# Dual_Motor_Driver.net
KiCad netlist of a schematic drawn in EAGLE
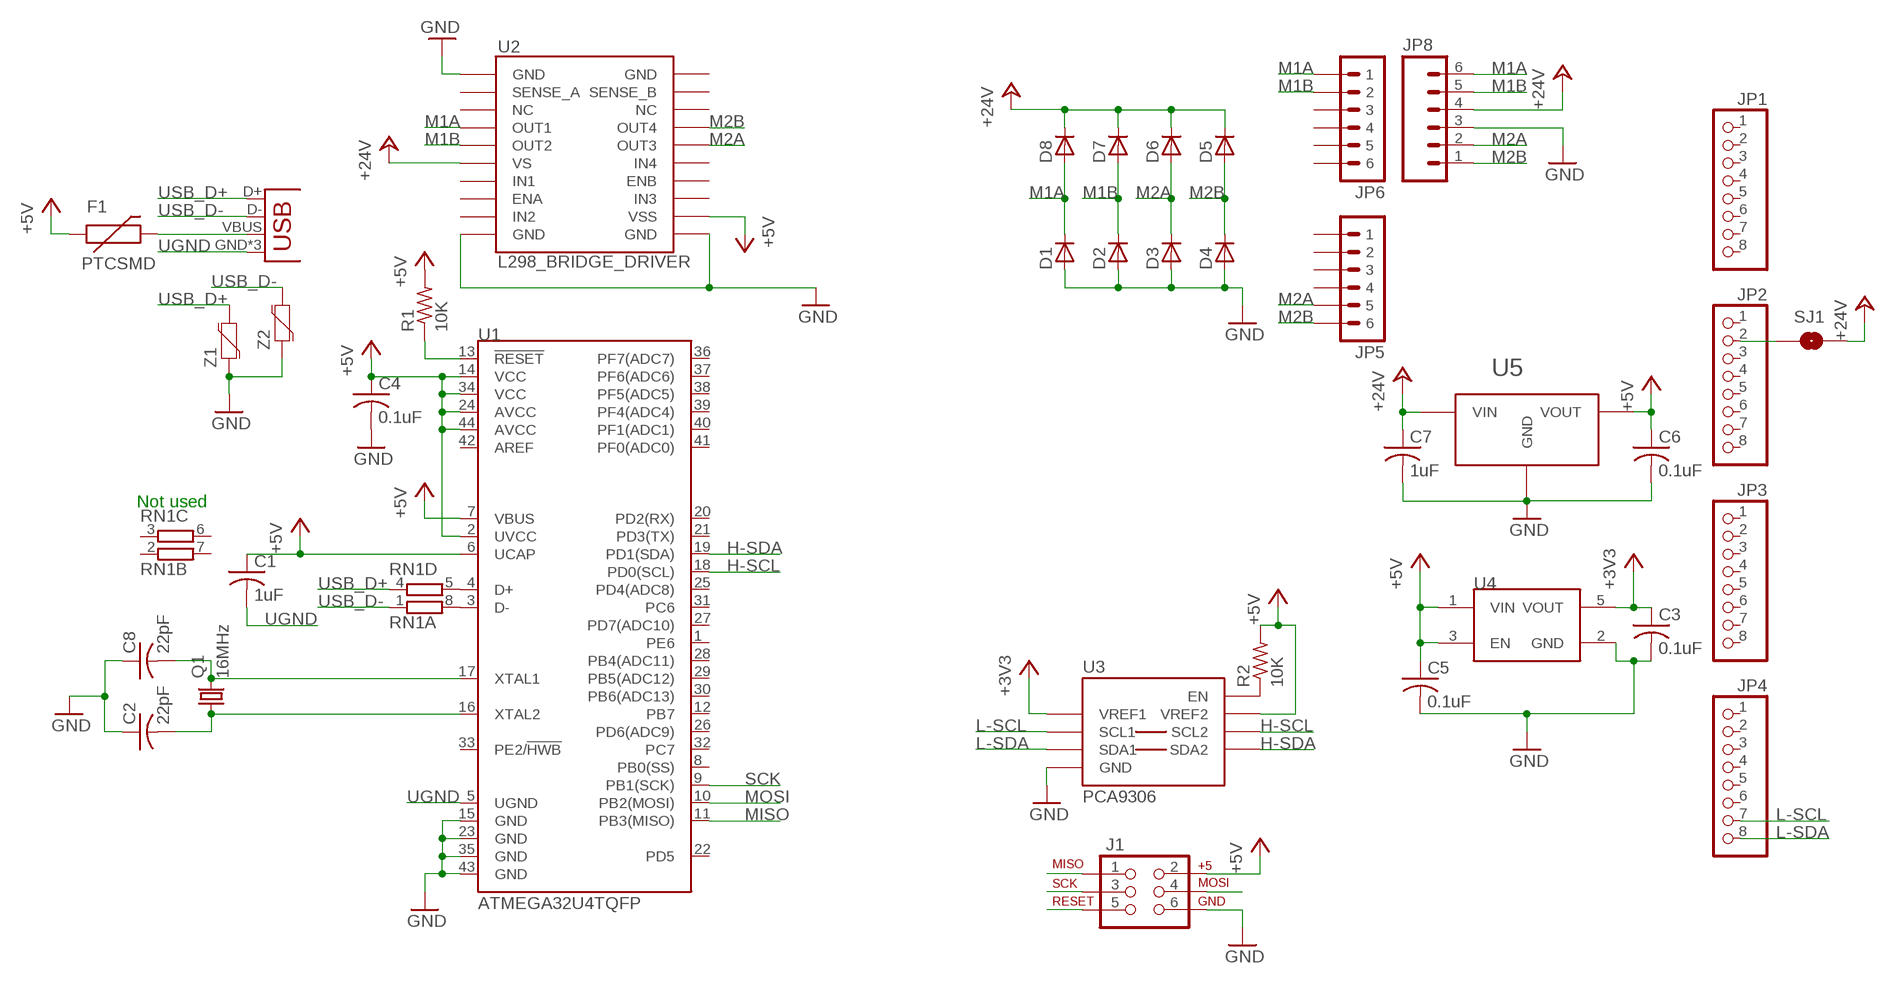
[diagram p0: schematic, sheet 1]

(export (version "E")
  (design (tool "Eeschema 10.0.6"))
  (components
    (comp (ref "C1")
      (value "1uF")
      (footprint "eagle-import:C0603")
      (libsource (lib "eagle-import") (part "C-USC0603"))
    )
    (comp (ref "C2")
      (value "22pF")
      (footprint "eagle-import:C0603")
      (libsource (lib "eagle-import") (part "C-USC0603"))
    )
    (comp (ref "C3")
      (value "0.1uF")
      (footprint "eagle-import:C0603")
      (libsource (lib "eagle-import") (part "C-USC0603"))
    )
    (comp (ref "C4")
      (value "0.1uF")
      (footprint "eagle-import:C0603")
      (libsource (lib "eagle-import") (part "C-USC0603"))
    )
    (comp (ref "C5")
      (value "0.1uF")
      (footprint "eagle-import:C0603")
      (libsource (lib "eagle-import") (part "C-USC0603"))
    )
    (comp (ref "C6")
      (value "0.1uF")
      (footprint "eagle-import:C0603")
      (libsource (lib "eagle-import") (part "C-USC0603"))
    )
    (comp (ref "C7")
      (value "1uF")
      (footprint "eagle-import:C0603")
      (libsource (lib "eagle-import") (part "C-USC0603"))
    )
    (comp (ref "C8")
      (value "22pF")
      (footprint "eagle-import:C0603")
      (libsource (lib "eagle-import") (part "C-USC0603"))
    )
    (comp (ref "D1")
      (value "D-SOD123")
      (footprint "eagle-import:SOD123")
      (fields (field (name "PART#") "CDBW140-G"))
      (libsource (lib "eagle-import") (part "D-SOD123"))
    )
    (comp (ref "D2")
      (value "D-SOD123")
      (footprint "eagle-import:SOD123")
      (fields (field (name "PART#") "CDBW140-G"))
      (libsource (lib "eagle-import") (part "D-SOD123"))
    )
    (comp (ref "D3")
      (value "D-SOD123")
      (footprint "eagle-import:SOD123")
      (fields (field (name "PART#") "CDBW140-G"))
      (libsource (lib "eagle-import") (part "D-SOD123"))
    )
    (comp (ref "D4")
      (value "D-SOD123")
      (footprint "eagle-import:SOD123")
      (fields (field (name "PART#") "CDBW140-G"))
      (libsource (lib "eagle-import") (part "D-SOD123"))
    )
    (comp (ref "D5")
      (value "D-SOD123")
      (footprint "eagle-import:SOD123")
      (fields (field (name "PART#") "CDBW140-G"))
      (libsource (lib "eagle-import") (part "D-SOD123"))
    )
    (comp (ref "D6")
      (value "D-SOD123")
      (footprint "eagle-import:SOD123")
      (fields (field (name "PART#") "CDBW140-G"))
      (libsource (lib "eagle-import") (part "D-SOD123"))
    )
    (comp (ref "D7")
      (value "D-SOD123")
      (footprint "eagle-import:SOD123")
      (fields (field (name "PART#") "CDBW140-G"))
      (libsource (lib "eagle-import") (part "D-SOD123"))
    )
    (comp (ref "D8")
      (value "D-SOD123")
      (footprint "eagle-import:SOD123")
      (fields (field (name "PART#") "CDBW140-G"))
      (libsource (lib "eagle-import") (part "D-SOD123"))
    )
    (comp (ref "F1")
      (value "PTCSMD")
      (footprint "eagle-import:PTC-1206")
      (fields (field (name "PART#") "0ZCJ0050FF2G"))
      (libsource (lib "eagle-import") (part "PTCSMD"))
    )
    (comp (ref "J1")
      (value "AVR_SPI_PRG_6PTH")
      (footprint "eagle-import:2X3")
      (libsource (lib "eagle-import") (part "AVR_SPI_PRG_6PTH"))
    )
    (comp (ref "JP1")
      (value "PINHD-1X81X08_NO_SILK")
      (footprint "eagle-import:1X08_NO_SS")
      (libsource (lib "eagle-import") (part "PINHD-1X81X08_NO_SILK"))
    )
    (comp (ref "JP2")
      (value "PINHD-1X81X08_NO_SILK")
      (footprint "eagle-import:1X08_NO_SS")
      (libsource (lib "eagle-import") (part "PINHD-1X81X08_NO_SILK"))
    )
    (comp (ref "JP3")
      (value "PINHD-1X81X08_NO_SILK")
      (footprint "eagle-import:1X08_NO_SS")
      (libsource (lib "eagle-import") (part "PINHD-1X81X08_NO_SILK"))
    )
    (comp (ref "JP4")
      (value "PINHD-1X81X08_NO_SILK")
      (footprint "eagle-import:1X08_NO_SS")
      (libsource (lib "eagle-import") (part "PINHD-1X81X08_NO_SILK"))
    )
    (comp (ref "JP5")
      (value "6PIN-SH_RIGHT_ANGLE")
      (footprint "eagle-import:6PIN-SH_SERIES_RA")
      (fields (field (name "PART#") "SM06B-SRSS-TB(LF)(SN)"))
      (libsource (lib "eagle-import") (part "6PIN-SH_RIGHT_ANGLE"))
    )
    (comp (ref "JP6")
      (value "6PIN-SH_RIGHT_ANGLE")
      (footprint "eagle-import:6PIN-SH_SERIES_RA")
      (fields (field (name "PART#") "SM06B-SRSS-TB(LF)(SN)"))
      (libsource (lib "eagle-import") (part "6PIN-SH_RIGHT_ANGLE"))
    )
    (comp (ref "JP7")
      (value "USB-MICROB")
      (footprint "eagle-import:USB-MICROB")
      (libsource (lib "eagle-import") (part "USB-MICROB"))
    )
    (comp (ref "JP8")
      (value "M063.5MM-6")
      (footprint "eagle-import:SCREWTERMINAL-3.5MM-6")
      (libsource (lib "eagle-import") (part "M063.5MM-6"))
    )
    (comp (ref "Q1")
      (value "16MHz")
      (footprint "eagle-import:CTS406")
      (fields (field (name "PART#") "406C35D16M00000"))
      (libsource (lib "eagle-import") (part "CRYSTALCTS406"))
    )
    (comp (ref "R1")
      (value "10K")
      (footprint "eagle-import:R0603")
      (libsource (lib "eagle-import") (part "R-US_R0603"))
    )
    (comp (ref "R2")
      (value "10K")
      (footprint "eagle-import:R0603")
      (libsource (lib "eagle-import") (part "R-US_R0603"))
    )
    (comp (ref "RN1")
      (value "4R-N0603-ARV")
      (footprint "eagle-import:0603-ARV")
      (libsource (lib "eagle-import") (part "4R-N0603-ARV"))
    )
    (comp (ref "SJ1")
      (value "SOLDERJUMPERNC")
      (footprint "eagle-import:SJ_2S")
      (libsource (lib "eagle-import") (part "SOLDERJUMPERNC"))
    )
    (comp (ref "U1")
      (value "ATMEGA32U4TQFP")
      (footprint "eagle-import:SPARKFUN-DIGITALIC_TQFP44")
      (libsource (lib "eagle-import") (part "ATMEGA32U4TQFP"))
    )
    (comp (ref "U2")
      (value "L298_BRIDGE_DRIVER")
      (footprint "eagle-import:POWERSO20")
      (libsource (lib "eagle-import") (part "L298_BRIDGE_DRIVER"))
    )
    (comp (ref "U3")
      (value "PCA9306")
      (footprint "eagle-import:SOIC-8")
      (fields (field (name "PART#") "PCA9306D,118"))
      (libsource (lib "eagle-import") (part "PCA9306"))
    )
    (comp (ref "U4")
      (value "TLV71333PDBVR")
      (footprint "eagle-import:SOT23-5")
      (libsource (lib "eagle-import") (part "ADP160"))
    )
    (comp (ref "U5")
      (value "VOLTAGE-REGULATOR")
      (footprint "eagle-import:SOT89")
      (fields (field (name "PART#") "L78L05ACUTR"))
      (libsource (lib "eagle-import") (part "VOLTAGE-REGULATOR"))
    )
    (comp (ref "Z1")
      (value "VARISTOR-0603")
      (footprint "eagle-import:0603-RES")
      (fields (field (name "PART#") "CG0603MLC-05E"))
      (libsource (lib "eagle-import") (part "VARISTOR-0603"))
    )
    (comp (ref "Z2")
      (value "VARISTOR-0603")
      (footprint "eagle-import:0603-RES")
      (fields (field (name "PART#") "CG0603MLC-05E"))
      (libsource (lib "eagle-import") (part "VARISTOR-0603"))
    )
  )
  (nets
    (net (code "1") (name "+3V3") (class "Default")
      (node (ref "C3") (pin "1") (pinfunction "1_1") (pintype "passive"))
      (node (ref "U3") (pin "P$2") (pinfunction "VREF1_P$2") (pintype "bidirectional"))
      (node (ref "U4") (pin "5") (pinfunction "VOUT_5") (pintype "bidirectional"))
    )
    (net (code "2") (name "+5V") (class "Default")
      (node (ref "C1") (pin "1") (pinfunction "1_1") (pintype "passive"))
      (node (ref "C4") (pin "1") (pinfunction "1_1") (pintype "passive"))
      (node (ref "C5") (pin "1") (pinfunction "1_1") (pintype "passive"))
      (node (ref "C6") (pin "1") (pinfunction "1_1") (pintype "passive"))
      (node (ref "F1") (pin "1") (pinfunction "1_1") (pintype "bidirectional"))
      (node (ref "J1") (pin "2") (pinfunction "2_2") (pintype "passive"))
      (node (ref "R1") (pin "2") (pinfunction "2_2") (pintype "passive"))
      (node (ref "R2") (pin "2") (pinfunction "2_2") (pintype "passive"))
      (node (ref "U1") (pin "14") (pinfunction "VCC_14") (pintype "bidirectional"))
      (node (ref "U1") (pin "2") (pinfunction "UVCC_2") (pintype "bidirectional"))
      (node (ref "U1") (pin "24") (pinfunction "AVCC_24") (pintype "bidirectional"))
      (node (ref "U1") (pin "34") (pinfunction "VCC_34") (pintype "bidirectional"))
      (node (ref "U1") (pin "44") (pinfunction "AVCC_44") (pintype "bidirectional"))
      (node (ref "U1") (pin "6") (pinfunction "UCAP_6") (pintype "bidirectional"))
      (node (ref "U1") (pin "7") (pinfunction "VBUS_7") (pintype "bidirectional"))
      (node (ref "U2") (pin "12") (pinfunction "VSS_12") (pintype "bidirectional"))
      (node (ref "U3") (pin "P$7") (pinfunction "VREF2_P$7") (pintype "bidirectional"))
      (node (ref "U4") (pin "1") (pinfunction "VIN_1") (pintype "bidirectional"))
      (node (ref "U4") (pin "3") (pinfunction "EN_3") (pintype "bidirectional"))
      (node (ref "U5") (pin "P$1") (pinfunction "VOUT_P$1") (pintype "bidirectional"))
    )
    (net (code "3") (name "+24V") (class "Default")
      (node (ref "C7") (pin "1") (pinfunction "1_1") (pintype "passive"))
      (node (ref "D5") (pin "1") (pinfunction "C_1") (pintype "passive"))
      (node (ref "D6") (pin "1") (pinfunction "C_1") (pintype "passive"))
      (node (ref "D7") (pin "1") (pinfunction "C_1") (pintype "passive"))
      (node (ref "D8") (pin "1") (pinfunction "C_1") (pintype "passive"))
      (node (ref "JP8") (pin "4") (pinfunction "4_4") (pintype "passive"))
      (node (ref "SJ1") (pin "2") (pinfunction "2_2") (pintype "passive"))
      (node (ref "U2") (pin "6") (pinfunction "VS_6") (pintype "bidirectional"))
      (node (ref "U5") (pin "P$3") (pinfunction "VIN_P$3") (pintype "bidirectional"))
    )
    (net (code "4") (name "/H-SCL") (class "Default")
      (node (ref "U1") (pin "18") (pinfunction "PD0(SCL)_18") (pintype "bidirectional"))
      (node (ref "U3") (pin "P$6") (pinfunction "SCL2_P$6") (pintype "bidirectional"))
    )
    (net (code "5") (name "/H-SDA") (class "Default")
      (node (ref "U1") (pin "19") (pinfunction "PD1(SDA)_19") (pintype "bidirectional"))
      (node (ref "U3") (pin "P$5") (pinfunction "SDA2_P$5") (pintype "bidirectional"))
    )
    (net (code "6") (name "/L-SCL") (class "Default")
      (node (ref "JP4") (pin "7") (pinfunction "7_7") (pintype "passive"))
      (node (ref "U3") (pin "P$3") (pinfunction "SCL1_P$3") (pintype "bidirectional"))
    )
    (net (code "7") (name "/L-SDA") (class "Default")
      (node (ref "JP4") (pin "8") (pinfunction "8_8") (pintype "passive"))
      (node (ref "U3") (pin "P$4") (pinfunction "SDA1_P$4") (pintype "bidirectional"))
    )
    (net (code "8") (name "/M1A") (class "Default")
      (node (ref "D1") (pin "1") (pinfunction "C_1") (pintype "passive"))
      (node (ref "D8") (pin "2") (pinfunction "A_2") (pintype "passive"))
      (node (ref "JP6") (pin "P$1") (pinfunction "1_P$1") (pintype "passive"))
      (node (ref "JP8") (pin "6") (pinfunction "6_6") (pintype "passive"))
      (node (ref "U2") (pin "4") (pinfunction "OUT1_4") (pintype "bidirectional"))
    )
    (net (code "9") (name "/M1B") (class "Default")
      (node (ref "D2") (pin "1") (pinfunction "C_1") (pintype "passive"))
      (node (ref "D7") (pin "2") (pinfunction "A_2") (pintype "passive"))
      (node (ref "JP6") (pin "P$2") (pinfunction "2_P$2") (pintype "passive"))
      (node (ref "JP8") (pin "5") (pinfunction "5_5") (pintype "passive"))
      (node (ref "U2") (pin "5") (pinfunction "OUT2_5") (pintype "bidirectional"))
    )
    (net (code "10") (name "/M2A") (class "Default")
      (node (ref "D3") (pin "1") (pinfunction "C_1") (pintype "passive"))
      (node (ref "D6") (pin "2") (pinfunction "A_2") (pintype "passive"))
      (node (ref "JP5") (pin "P$5") (pinfunction "5_P$5") (pintype "passive"))
      (node (ref "JP8") (pin "2") (pinfunction "2_2") (pintype "passive"))
      (node (ref "U2") (pin "16") (pinfunction "OUT3_16") (pintype "bidirectional"))
    )
    (net (code "11") (name "/M2B") (class "Default")
      (node (ref "D4") (pin "1") (pinfunction "C_1") (pintype "passive"))
      (node (ref "D5") (pin "2") (pinfunction "A_2") (pintype "passive"))
      (node (ref "JP5") (pin "P$6") (pinfunction "6_P$6") (pintype "passive"))
      (node (ref "JP8") (pin "1") (pinfunction "1_1") (pintype "passive"))
      (node (ref "U2") (pin "17") (pinfunction "OUT4_17") (pintype "bidirectional"))
    )
    (net (code "12") (name "/MISO") (class "Default")
      (node (ref "J1") (pin "1") (pinfunction "1_1") (pintype "passive"))
      (node (ref "U1") (pin "11") (pinfunction "PB3(MISO)_11") (pintype "bidirectional"))
    )
    (net (code "13") (name "/MOSI") (class "Default")
      (node (ref "J1") (pin "4") (pinfunction "4_4") (pintype "passive"))
      (node (ref "U1") (pin "10") (pinfunction "PB2(MOSI)_10") (pintype "bidirectional"))
    )
    (net (code "14") (name "/RESET") (class "Default")
      (node (ref "J1") (pin "5") (pinfunction "5_5") (pintype "passive"))
      (node (ref "R1") (pin "1") (pinfunction "1_1") (pintype "passive"))
      (node (ref "U1") (pin "13") (pinfunction "~{RESET}_13") (pintype "bidirectional"))
    )
    (net (code "15") (name "/SCK") (class "Default")
      (node (ref "J1") (pin "3") (pinfunction "3_3") (pintype "passive"))
      (node (ref "U1") (pin "9") (pinfunction "PB1(SCK)_9") (pintype "bidirectional"))
    )
    (net (code "16") (name "/UGND") (class "Default")
      (node (ref "C1") (pin "2") (pinfunction "2_2") (pintype "passive"))
      (node (ref "JP7") (pin "GND") (pinfunction "GND_GND") (pintype "bidirectional"))
      (node (ref "JP7") (pin "MT1") (pinfunction "GND_MT1") (pintype "bidirectional"))
      (node (ref "JP7") (pin "MT2") (pinfunction "GND_MT2") (pintype "bidirectional"))
      (node (ref "U1") (pin "5") (pinfunction "UGND_5") (pintype "bidirectional"))
    )
    (net (code "17") (name "/USB_D+") (class "Default")
      (node (ref "JP7") (pin "D+") (pinfunction "D+_D+") (pintype "bidirectional"))
      (node (ref "RN1") (pin "4") (pinfunction "1_4") (pintype "passive"))
      (node (ref "Z1") (pin "2") (pinfunction "2_2") (pintype "passive"))
    )
    (net (code "18") (name "/USB_D-") (class "Default")
      (node (ref "JP7") (pin "D-") (pinfunction "D-_D-") (pintype "bidirectional"))
      (node (ref "RN1") (pin "1") (pinfunction "1_1") (pintype "passive"))
      (node (ref "Z2") (pin "2") (pinfunction "2_2") (pintype "passive"))
    )
    (net (code "19") (name "GND") (class "Default")
      (node (ref "C2") (pin "1") (pinfunction "1_1") (pintype "passive"))
      (node (ref "C3") (pin "2") (pinfunction "2_2") (pintype "passive"))
      (node (ref "C4") (pin "2") (pinfunction "2_2") (pintype "passive"))
      (node (ref "C5") (pin "2") (pinfunction "2_2") (pintype "passive"))
      (node (ref "C6") (pin "2") (pinfunction "2_2") (pintype "passive"))
      (node (ref "C7") (pin "2") (pinfunction "2_2") (pintype "passive"))
      (node (ref "C8") (pin "1") (pinfunction "1_1") (pintype "passive"))
      (node (ref "D1") (pin "2") (pinfunction "A_2") (pintype "passive"))
      (node (ref "D2") (pin "2") (pinfunction "A_2") (pintype "passive"))
      (node (ref "D3") (pin "2") (pinfunction "A_2") (pintype "passive"))
      (node (ref "D4") (pin "2") (pinfunction "A_2") (pintype "passive"))
      (node (ref "J1") (pin "6") (pinfunction "6_6") (pintype "passive"))
      (node (ref "JP8") (pin "3") (pinfunction "3_3") (pintype "passive"))
      (node (ref "U1") (pin "15") (pinfunction "GND_15") (pintype "bidirectional"))
      (node (ref "U1") (pin "23") (pinfunction "GND_23") (pintype "bidirectional"))
      (node (ref "U1") (pin "35") (pinfunction "GND_35") (pintype "bidirectional"))
      (node (ref "U1") (pin "43") (pinfunction "GND_43") (pintype "bidirectional"))
      (node (ref "U2") (pin "1") (pinfunction "GND_1") (pintype "bidirectional"))
      (node (ref "U2") (pin "10") (pinfunction "GND_10") (pintype "bidirectional"))
      (node (ref "U2") (pin "11") (pinfunction "GND_11") (pintype "bidirectional"))
      (node (ref "U3") (pin "P$1") (pinfunction "GND_P$1") (pintype "bidirectional"))
      (node (ref "U4") (pin "2") (pinfunction "GND_2") (pintype "bidirectional"))
      (node (ref "U5") (pin "P$2") (pinfunction "GND_P$2") (pintype "bidirectional"))
      (node (ref "U5") (pin "P$4") (pinfunction "GND_P$4") (pintype "bidirectional"))
      (node (ref "Z1") (pin "1") (pinfunction "1_1") (pintype "passive"))
      (node (ref "Z2") (pin "1") (pinfunction "1_1") (pintype "passive"))
    )
    (net (code "20") (name "Net-(F1-Pad2)") (class "Default")
      (node (ref "F1") (pin "2") (pinfunction "2_2") (pintype "bidirectional"))
      (node (ref "JP7") (pin "VBUS") (pinfunction "VBUS_VBUS") (pintype "bidirectional"))
    )
    (net (code "21") (name "Net-(JP2-Pad2)") (class "Default")
      (node (ref "JP2") (pin "2") (pinfunction "2_2") (pintype "passive"))
      (node (ref "SJ1") (pin "1") (pinfunction "1_1") (pintype "passive"))
    )
    (net (code "22") (name "Net-(Q1-2)") (class "Default")
      (node (ref "C8") (pin "2") (pinfunction "2_2") (pintype "passive"))
      (node (ref "Q1") (pin "3") (pinfunction "2_3") (pintype "passive"))
      (node (ref "U1") (pin "17") (pinfunction "XTAL1_17") (pintype "bidirectional"))
    )
    (net (code "23") (name "Net-(RN1A-2)") (class "Default")
      (node (ref "RN1") (pin "8") (pinfunction "2_8") (pintype "passive"))
      (node (ref "U1") (pin "3") (pinfunction "D-_3") (pintype "bidirectional"))
    )
    (net (code "24") (name "Net-(RN1D-2)") (class "Default")
      (node (ref "RN1") (pin "5") (pinfunction "2_5") (pintype "passive"))
      (node (ref "U1") (pin "4") (pinfunction "D+_4") (pintype "bidirectional"))
    )
    (net (code "25") (name "Net-(U1-XTAL2)") (class "Default")
      (node (ref "C2") (pin "2") (pinfunction "2_2") (pintype "passive"))
      (node (ref "Q1") (pin "1") (pinfunction "1_1") (pintype "passive"))
      (node (ref "U1") (pin "16") (pinfunction "XTAL2_16") (pintype "bidirectional"))
    )
    (net (code "26") (name "Net-(U3-EN)") (class "Default")
      (node (ref "R2") (pin "1") (pinfunction "1_1") (pintype "passive"))
      (node (ref "U3") (pin "P$8") (pinfunction "EN_P$8") (pintype "bidirectional"))
    )
    (net (code "27") (name "unconnected-(JP1-Pad1)") (class "Default")
      (node (ref "JP1") (pin "1") (pinfunction "1_1") (pintype "passive"))
    )
    (net (code "28") (name "unconnected-(JP1-Pad2)") (class "Default")
      (node (ref "JP1") (pin "2") (pinfunction "2_2") (pintype "passive"))
    )
    (net (code "29") (name "unconnected-(JP1-Pad3)") (class "Default")
      (node (ref "JP1") (pin "3") (pinfunction "3_3") (pintype "passive"))
    )
    (net (code "30") (name "unconnected-(JP1-Pad4)") (class "Default")
      (node (ref "JP1") (pin "4") (pinfunction "4_4") (pintype "passive"))
    )
    (net (code "31") (name "unconnected-(JP1-Pad5)") (class "Default")
      (node (ref "JP1") (pin "5") (pinfunction "5_5") (pintype "passive"))
    )
    (net (code "32") (name "unconnected-(JP1-Pad6)") (class "Default")
      (node (ref "JP1") (pin "6") (pinfunction "6_6") (pintype "passive"))
    )
    (net (code "33") (name "unconnected-(JP1-Pad7)") (class "Default")
      (node (ref "JP1") (pin "7") (pinfunction "7_7") (pintype "passive"))
    )
    (net (code "34") (name "unconnected-(JP1-Pad8)") (class "Default")
      (node (ref "JP1") (pin "8") (pinfunction "8_8") (pintype "passive"))
    )
    (net (code "35") (name "unconnected-(JP2-Pad1)") (class "Default")
      (node (ref "JP2") (pin "1") (pinfunction "1_1") (pintype "passive"))
    )
    (net (code "36") (name "unconnected-(JP2-Pad3)") (class "Default")
      (node (ref "JP2") (pin "3") (pinfunction "3_3") (pintype "passive"))
    )
    (net (code "37") (name "unconnected-(JP2-Pad4)") (class "Default")
      (node (ref "JP2") (pin "4") (pinfunction "4_4") (pintype "passive"))
    )
    (net (code "38") (name "unconnected-(JP2-Pad5)") (class "Default")
      (node (ref "JP2") (pin "5") (pinfunction "5_5") (pintype "passive"))
    )
    (net (code "39") (name "unconnected-(JP2-Pad6)") (class "Default")
      (node (ref "JP2") (pin "6") (pinfunction "6_6") (pintype "passive"))
    )
    (net (code "40") (name "unconnected-(JP2-Pad7)") (class "Default")
      (node (ref "JP2") (pin "7") (pinfunction "7_7") (pintype "passive"))
    )
    (net (code "41") (name "unconnected-(JP2-Pad8)") (class "Default")
      (node (ref "JP2") (pin "8") (pinfunction "8_8") (pintype "passive"))
    )
    (net (code "42") (name "unconnected-(JP3-Pad1)") (class "Default")
      (node (ref "JP3") (pin "1") (pinfunction "1_1") (pintype "passive"))
    )
    (net (code "43") (name "unconnected-(JP3-Pad2)") (class "Default")
      (node (ref "JP3") (pin "2") (pinfunction "2_2") (pintype "passive"))
    )
    (net (code "44") (name "unconnected-(JP3-Pad3)") (class "Default")
      (node (ref "JP3") (pin "3") (pinfunction "3_3") (pintype "passive"))
    )
    (net (code "45") (name "unconnected-(JP3-Pad4)") (class "Default")
      (node (ref "JP3") (pin "4") (pinfunction "4_4") (pintype "passive"))
    )
    (net (code "46") (name "unconnected-(JP3-Pad5)") (class "Default")
      (node (ref "JP3") (pin "5") (pinfunction "5_5") (pintype "passive"))
    )
    (net (code "47") (name "unconnected-(JP3-Pad6)") (class "Default")
      (node (ref "JP3") (pin "6") (pinfunction "6_6") (pintype "passive"))
    )
    (net (code "48") (name "unconnected-(JP3-Pad7)") (class "Default")
      (node (ref "JP3") (pin "7") (pinfunction "7_7") (pintype "passive"))
    )
    (net (code "49") (name "unconnected-(JP3-Pad8)") (class "Default")
      (node (ref "JP3") (pin "8") (pinfunction "8_8") (pintype "passive"))
    )
    (net (code "50") (name "unconnected-(JP4-Pad1)") (class "Default")
      (node (ref "JP4") (pin "1") (pinfunction "1_1") (pintype "passive"))
    )
    (net (code "51") (name "unconnected-(JP4-Pad2)") (class "Default")
      (node (ref "JP4") (pin "2") (pinfunction "2_2") (pintype "passive"))
    )
    (net (code "52") (name "unconnected-(JP4-Pad3)") (class "Default")
      (node (ref "JP4") (pin "3") (pinfunction "3_3") (pintype "passive"))
    )
    (net (code "53") (name "unconnected-(JP4-Pad4)") (class "Default")
      (node (ref "JP4") (pin "4") (pinfunction "4_4") (pintype "passive"))
    )
    (net (code "54") (name "unconnected-(JP4-Pad5)") (class "Default")
      (node (ref "JP4") (pin "5") (pinfunction "5_5") (pintype "passive"))
    )
    (net (code "55") (name "unconnected-(JP4-Pad6)") (class "Default")
      (node (ref "JP4") (pin "6") (pinfunction "6_6") (pintype "passive"))
    )
    (net (code "56") (name "unconnected-(JP5-1-PadP$1)") (class "Default")
      (node (ref "JP5") (pin "P$1") (pinfunction "1_P$1") (pintype "passive"))
    )
    (net (code "57") (name "unconnected-(JP5-2-PadP$2)") (class "Default")
      (node (ref "JP5") (pin "P$2") (pinfunction "2_P$2") (pintype "passive"))
    )
    (net (code "58") (name "unconnected-(JP5-3-PadP$3)") (class "Default")
      (node (ref "JP5") (pin "P$3") (pinfunction "3_P$3") (pintype "passive"))
    )
    (net (code "59") (name "unconnected-(JP5-4-PadP$4)") (class "Default")
      (node (ref "JP5") (pin "P$4") (pinfunction "4_P$4") (pintype "passive"))
    )
    (net (code "60") (name "unconnected-(JP6-3-PadP$3)") (class "Default")
      (node (ref "JP6") (pin "P$3") (pinfunction "3_P$3") (pintype "passive"))
    )
    (net (code "61") (name "unconnected-(JP6-4-PadP$4)") (class "Default")
      (node (ref "JP6") (pin "P$4") (pinfunction "4_P$4") (pintype "passive"))
    )
    (net (code "62") (name "unconnected-(JP6-5-PadP$5)") (class "Default")
      (node (ref "JP6") (pin "P$5") (pinfunction "5_P$5") (pintype "passive"))
    )
    (net (code "63") (name "unconnected-(JP6-6-PadP$6)") (class "Default")
      (node (ref "JP6") (pin "P$6") (pinfunction "6_P$6") (pintype "passive"))
    )
    (net (code "64") (name "unconnected-(RN1B-1-Pad2)") (class "Default")
      (node (ref "RN1") (pin "2") (pinfunction "1_2") (pintype "passive"))
    )
    (net (code "65") (name "unconnected-(RN1B-2-Pad7)") (class "Default")
      (node (ref "RN1") (pin "7") (pinfunction "2_7") (pintype "passive"))
    )
    (net (code "66") (name "unconnected-(RN1C-1-Pad3)") (class "Default")
      (node (ref "RN1") (pin "3") (pinfunction "1_3") (pintype "passive"))
    )
    (net (code "67") (name "unconnected-(RN1C-2-Pad6)") (class "Default")
      (node (ref "RN1") (pin "6") (pinfunction "2_6") (pintype "passive"))
    )
    (net (code "68") (name "unconnected-(U1-AREF-Pad42)") (class "Default")
      (node (ref "U1") (pin "42") (pinfunction "AREF_42") (pintype "bidirectional"))
    )
    (net (code "69") (name "unconnected-(U1-PB0(SS)-Pad8)") (class "Default")
      (node (ref "U1") (pin "8") (pinfunction "PB0(SS)_8") (pintype "bidirectional"))
    )
    (net (code "70") (name "unconnected-(U1-PB4(ADC11)-Pad28)") (class "Default")
      (node (ref "U1") (pin "28") (pinfunction "PB4(ADC11)_28") (pintype "bidirectional"))
    )
    (net (code "71") (name "unconnected-(U1-PB5(ADC12)-Pad29)") (class "Default")
      (node (ref "U1") (pin "29") (pinfunction "PB5(ADC12)_29") (pintype "bidirectional"))
    )
    (net (code "72") (name "unconnected-(U1-PB6(ADC13)-Pad30)") (class "Default")
      (node (ref "U1") (pin "30") (pinfunction "PB6(ADC13)_30") (pintype "bidirectional"))
    )
    (net (code "73") (name "unconnected-(U1-PB7-Pad12)") (class "Default")
      (node (ref "U1") (pin "12") (pinfunction "PB7_12") (pintype "bidirectional"))
    )
    (net (code "74") (name "unconnected-(U1-PC6-Pad31)") (class "Default")
      (node (ref "U1") (pin "31") (pinfunction "PC6_31") (pintype "bidirectional"))
    )
    (net (code "75") (name "unconnected-(U1-PC7-Pad32)") (class "Default")
      (node (ref "U1") (pin "32") (pinfunction "PC7_32") (pintype "bidirectional"))
    )
    (net (code "76") (name "unconnected-(U1-PD2(RX)-Pad20)") (class "Default")
      (node (ref "U1") (pin "20") (pinfunction "PD2(RX)_20") (pintype "bidirectional"))
    )
    (net (code "77") (name "unconnected-(U1-PD3(TX)-Pad21)") (class "Default")
      (node (ref "U1") (pin "21") (pinfunction "PD3(TX)_21") (pintype "bidirectional"))
    )
    (net (code "78") (name "unconnected-(U1-PD4(ADC8)-Pad25)") (class "Default")
      (node (ref "U1") (pin "25") (pinfunction "PD4(ADC8)_25") (pintype "bidirectional"))
    )
    (net (code "79") (name "unconnected-(U1-PD5-Pad22)") (class "Default")
      (node (ref "U1") (pin "22") (pinfunction "PD5_22") (pintype "bidirectional"))
    )
    (net (code "80") (name "unconnected-(U1-PD6(ADC9)-Pad26)") (class "Default")
      (node (ref "U1") (pin "26") (pinfunction "PD6(ADC9)_26") (pintype "bidirectional"))
    )
    (net (code "81") (name "unconnected-(U1-PD7(ADC10)-Pad27)") (class "Default")
      (node (ref "U1") (pin "27") (pinfunction "PD7(ADC10)_27") (pintype "bidirectional"))
    )
    (net (code "82") (name "unconnected-(U1-PE2{slash}~{HWB}-Pad33)") (class "Default")
      (node (ref "U1") (pin "33") (pinfunction "PE2/~{HWB}_33") (pintype "bidirectional"))
    )
    (net (code "83") (name "unconnected-(U1-PE6-Pad1)") (class "Default")
      (node (ref "U1") (pin "1") (pinfunction "PE6_1") (pintype "bidirectional"))
    )
    (net (code "84") (name "unconnected-(U1-PF0(ADC0)-Pad41)") (class "Default")
      (node (ref "U1") (pin "41") (pinfunction "PF0(ADC0)_41") (pintype "bidirectional"))
    )
    (net (code "85") (name "unconnected-(U1-PF1(ADC1)-Pad40)") (class "Default")
      (node (ref "U1") (pin "40") (pinfunction "PF1(ADC1)_40") (pintype "bidirectional"))
    )
    (net (code "86") (name "unconnected-(U1-PF4(ADC4)-Pad39)") (class "Default")
      (node (ref "U1") (pin "39") (pinfunction "PF4(ADC4)_39") (pintype "bidirectional"))
    )
    (net (code "87") (name "unconnected-(U1-PF5(ADC5)-Pad38)") (class "Default")
      (node (ref "U1") (pin "38") (pinfunction "PF5(ADC5)_38") (pintype "bidirectional"))
    )
    (net (code "88") (name "unconnected-(U1-PF6(ADC6)-Pad37)") (class "Default")
      (node (ref "U1") (pin "37") (pinfunction "PF6(ADC6)_37") (pintype "bidirectional"))
    )
    (net (code "89") (name "unconnected-(U1-PF7(ADC7)-Pad36)") (class "Default")
      (node (ref "U1") (pin "36") (pinfunction "PF7(ADC7)_36") (pintype "bidirectional"))
    )
    (net (code "90") (name "unconnected-(U2-ENA-Pad8)") (class "Default")
      (node (ref "U2") (pin "8") (pinfunction "ENA_8") (pintype "bidirectional"))
    )
    (net (code "91") (name "unconnected-(U2-ENB-Pad14)") (class "Default")
      (node (ref "U2") (pin "14") (pinfunction "ENB_14") (pintype "bidirectional"))
    )
    (net (code "92") (name "unconnected-(U2-GND-Pad20)") (class "Default")
      (node (ref "U2") (pin "20") (pinfunction "GND_20") (pintype "bidirectional"))
    )
    (net (code "93") (name "unconnected-(U2-IN1-Pad7)") (class "Default")
      (node (ref "U2") (pin "7") (pinfunction "IN1_7") (pintype "bidirectional"))
    )
    (net (code "94") (name "unconnected-(U2-IN2-Pad9)") (class "Default")
      (node (ref "U2") (pin "9") (pinfunction "IN2_9") (pintype "bidirectional"))
    )
    (net (code "95") (name "unconnected-(U2-IN3-Pad13)") (class "Default")
      (node (ref "U2") (pin "13") (pinfunction "IN3_13") (pintype "bidirectional"))
    )
    (net (code "96") (name "unconnected-(U2-IN4-Pad15)") (class "Default")
      (node (ref "U2") (pin "15") (pinfunction "IN4_15") (pintype "bidirectional"))
    )
    (net (code "97") (name "unconnected-(U2-NC-Pad3)") (class "Default")
      (node (ref "U2") (pin "3") (pinfunction "NC_3") (pintype "bidirectional"))
    )
    (net (code "98") (name "unconnected-(U2-NC-Pad18)") (class "Default")
      (node (ref "U2") (pin "18") (pinfunction "NC_18") (pintype "bidirectional"))
    )
    (net (code "99") (name "unconnected-(U2-SENSE_A-Pad2)") (class "Default")
      (node (ref "U2") (pin "2") (pinfunction "SENSE_A_2") (pintype "bidirectional"))
    )
    (net (code "100") (name "unconnected-(U2-SENSE_B-Pad19)") (class "Default")
      (node (ref "U2") (pin "19") (pinfunction "SENSE_B_19") (pintype "bidirectional"))
    )
  )
)
